# BMCOP.net
KiCad netlist of a schematic drawn in EAGLE
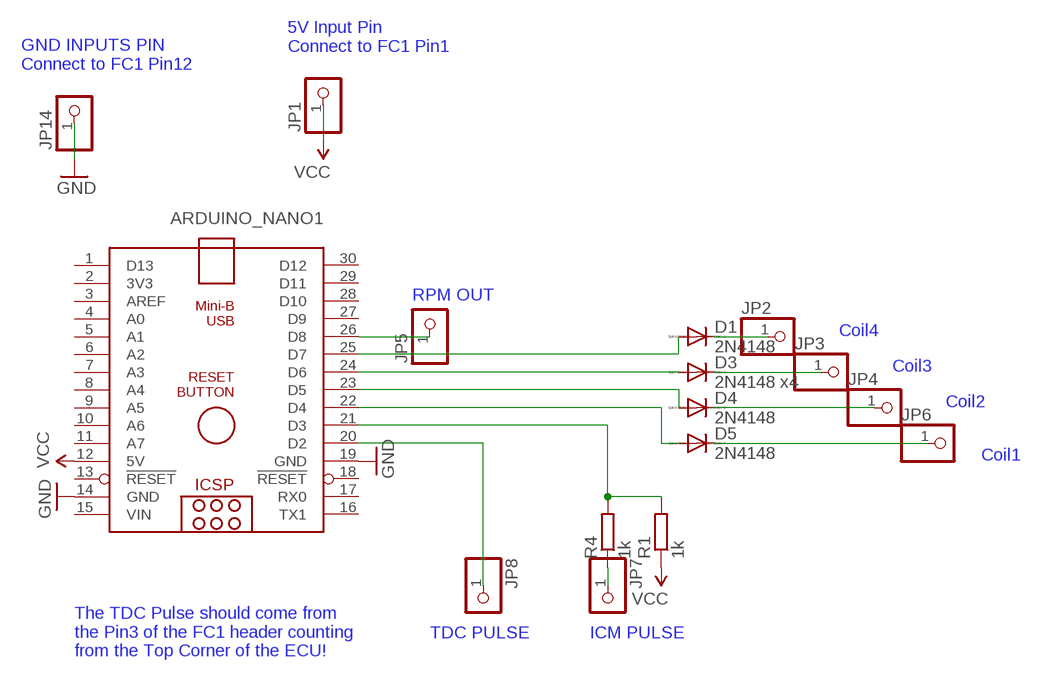
[diagram p0: schematic, sheet 1]

(export (version "E")
  (design (tool "Eeschema 10.0.6"))
  (components
    (comp (ref "ARDUINO_NANO1")
      (value "ARDUINO_NANO")
      (footprint "eagle-import:ARDUINO_NANO")
      (libsource (lib "eagle-import") (part "ARDUINO_NANO"))
    )
    (comp (ref "D1")
      (value "2N4148")
      (footprint "eagle-import:D-7.5")
      (libsource (lib "eagle-import") (part "DIODE-D-7.5"))
    )
    (comp (ref "D3")
      (value "2N4148 x4")
      (footprint "eagle-import:D-7.5")
      (libsource (lib "eagle-import") (part "DIODE-D-7.5"))
    )
    (comp (ref "D4")
      (value "2N4148")
      (footprint "eagle-import:D-7.5")
      (libsource (lib "eagle-import") (part "DIODE-D-7.5"))
    )
    (comp (ref "D5")
      (value "2N4148")
      (footprint "eagle-import:D-7.5")
      (libsource (lib "eagle-import") (part "DIODE-D-7.5"))
    )
    (comp (ref "JP1")
      (value "PINHD-1X1")
      (footprint "eagle-import:1X01")
      (libsource (lib "eagle-import") (part "PINHD-1X1"))
    )
    (comp (ref "JP2")
      (value "PINHD-1X1")
      (footprint "eagle-import:1X01")
      (libsource (lib "eagle-import") (part "PINHD-1X1"))
    )
    (comp (ref "JP3")
      (value "PINHD-1X1")
      (footprint "eagle-import:1X01")
      (libsource (lib "eagle-import") (part "PINHD-1X1"))
    )
    (comp (ref "JP4")
      (value "PINHD-1X1")
      (footprint "eagle-import:1X01")
      (libsource (lib "eagle-import") (part "PINHD-1X1"))
    )
    (comp (ref "JP5")
      (value "PINHD-1X1")
      (footprint "eagle-import:1X01")
      (libsource (lib "eagle-import") (part "PINHD-1X1"))
    )
    (comp (ref "JP6")
      (value "PINHD-1X1")
      (footprint "eagle-import:1X01")
      (libsource (lib "eagle-import") (part "PINHD-1X1"))
    )
    (comp (ref "JP7")
      (value "PINHD-1X1")
      (footprint "eagle-import:1X01")
      (libsource (lib "eagle-import") (part "PINHD-1X1"))
    )
    (comp (ref "JP8")
      (value "PINHD-1X1")
      (footprint "eagle-import:1X01")
      (libsource (lib "eagle-import") (part "PINHD-1X1"))
    )
    (comp (ref "JP14")
      (value "PINHD-1X1")
      (footprint "eagle-import:1X01")
      (libsource (lib "eagle-import") (part "PINHD-1X1"))
    )
    (comp (ref "R1")
      (value "1k")
      (footprint "eagle-import:0204_7")
      (libsource (lib "eagle-import") (part "R-EU_0204/7"))
    )
    (comp (ref "R4")
      (value "1k")
      (footprint "eagle-import:0204_7")
      (libsource (lib "eagle-import") (part "R-EU_0204/7"))
    )
  )
  (nets
    (net (code "1") (name "/VIN") (class "Default")
      (node (ref "ARDUINO_NANO1") (pin "15") (pinfunction "VIN_15") (pintype "power_in"))
    )
    (net (code "2") (name "GND") (class "Default")
      (node (ref "ARDUINO_NANO1") (pin "14") (pinfunction "GND_14") (pintype "power_in"))
      (node (ref "ARDUINO_NANO1") (pin "19") (pinfunction "GND_19") (pintype "power_in"))
      (node (ref "JP14") (pin "1") (pinfunction "1_1") (pintype "passive"))
    )
    (net (code "3") (name "Net-(ARDUINO_NANO1-D2)") (class "Default")
      (node (ref "ARDUINO_NANO1") (pin "20") (pinfunction "D2_20") (pintype "bidirectional"))
      (node (ref "JP8") (pin "1") (pinfunction "1_1") (pintype "passive"))
    )
    (net (code "4") (name "Net-(ARDUINO_NANO1-D3)") (class "Default")
      (node (ref "ARDUINO_NANO1") (pin "21") (pinfunction "D3_21") (pintype "bidirectional"))
      (node (ref "R1") (pin "2") (pinfunction "2_2") (pintype "passive"))
      (node (ref "R4") (pin "2") (pinfunction "2_2") (pintype "passive"))
    )
    (net (code "5") (name "Net-(ARDUINO_NANO1-D4)") (class "Default")
      (node (ref "ARDUINO_NANO1") (pin "22") (pinfunction "D4_22") (pintype "bidirectional"))
      (node (ref "D5") (pin "A") (pinfunction "A_A") (pintype "passive"))
    )
    (net (code "6") (name "Net-(ARDUINO_NANO1-D5)") (class "Default")
      (node (ref "ARDUINO_NANO1") (pin "23") (pinfunction "D5_23") (pintype "bidirectional"))
      (node (ref "D4") (pin "A") (pinfunction "A_A") (pintype "passive"))
    )
    (net (code "7") (name "Net-(ARDUINO_NANO1-D6)") (class "Default")
      (node (ref "ARDUINO_NANO1") (pin "24") (pinfunction "D6_24") (pintype "bidirectional"))
      (node (ref "D3") (pin "A") (pinfunction "A_A") (pintype "passive"))
    )
    (net (code "8") (name "Net-(ARDUINO_NANO1-D7)") (class "Default")
      (node (ref "ARDUINO_NANO1") (pin "25") (pinfunction "D7_25") (pintype "bidirectional"))
      (node (ref "D1") (pin "A") (pinfunction "A_A") (pintype "passive"))
    )
    (net (code "9") (name "Net-(ARDUINO_NANO1-D8)") (class "Default")
      (node (ref "ARDUINO_NANO1") (pin "26") (pinfunction "D8_26") (pintype "bidirectional"))
      (node (ref "JP5") (pin "1") (pinfunction "1_1") (pintype "passive"))
    )
    (net (code "10") (name "Net-(D1-PadC)") (class "Default")
      (node (ref "D1") (pin "C") (pinfunction "C_C") (pintype "passive"))
      (node (ref "JP2") (pin "1") (pinfunction "1_1") (pintype "passive"))
    )
    (net (code "11") (name "Net-(D3-PadC)") (class "Default")
      (node (ref "D3") (pin "C") (pinfunction "C_C") (pintype "passive"))
      (node (ref "JP3") (pin "1") (pinfunction "1_1") (pintype "passive"))
    )
    (net (code "12") (name "Net-(D4-PadC)") (class "Default")
      (node (ref "D4") (pin "C") (pinfunction "C_C") (pintype "passive"))
      (node (ref "JP4") (pin "1") (pinfunction "1_1") (pintype "passive"))
    )
    (net (code "13") (name "Net-(D5-PadC)") (class "Default")
      (node (ref "D5") (pin "C") (pinfunction "C_C") (pintype "passive"))
      (node (ref "JP6") (pin "1") (pinfunction "1_1") (pintype "passive"))
    )
    (net (code "14") (name "Net-(JP7-Pad1)") (class "Default")
      (node (ref "JP7") (pin "1") (pinfunction "1_1") (pintype "passive"))
      (node (ref "R4") (pin "1") (pinfunction "1_1") (pintype "passive"))
    )
    (net (code "15") (name "VCC") (class "Default")
      (node (ref "ARDUINO_NANO1") (pin "12") (pinfunction "5V_12") (pintype "power_in"))
      (node (ref "JP1") (pin "1") (pinfunction "1_1") (pintype "passive"))
      (node (ref "R1") (pin "1") (pinfunction "1_1") (pintype "passive"))
    )
    (net (code "16") (name "unconnected-(ARDUINO_NANO1-3V3-Pad2)") (class "Default")
      (node (ref "ARDUINO_NANO1") (pin "2") (pinfunction "3V3_2") (pintype "output"))
    )
    (net (code "17") (name "unconnected-(ARDUINO_NANO1-A0-Pad4)") (class "Default")
      (node (ref "ARDUINO_NANO1") (pin "4") (pinfunction "A0_4") (pintype "bidirectional"))
    )
    (net (code "18") (name "unconnected-(ARDUINO_NANO1-A1-Pad5)") (class "Default")
      (node (ref "ARDUINO_NANO1") (pin "5") (pinfunction "A1_5") (pintype "bidirectional"))
    )
    (net (code "19") (name "unconnected-(ARDUINO_NANO1-A2-Pad6)") (class "Default")
      (node (ref "ARDUINO_NANO1") (pin "6") (pinfunction "A2_6") (pintype "bidirectional"))
    )
    (net (code "20") (name "unconnected-(ARDUINO_NANO1-A3-Pad7)") (class "Default")
      (node (ref "ARDUINO_NANO1") (pin "7") (pinfunction "A3_7") (pintype "bidirectional"))
    )
    (net (code "21") (name "unconnected-(ARDUINO_NANO1-A4-Pad8)") (class "Default")
      (node (ref "ARDUINO_NANO1") (pin "8") (pinfunction "A4_8") (pintype "bidirectional"))
    )
    (net (code "22") (name "unconnected-(ARDUINO_NANO1-A5-Pad9)") (class "Default")
      (node (ref "ARDUINO_NANO1") (pin "9") (pinfunction "A5_9") (pintype "bidirectional"))
    )
    (net (code "23") (name "unconnected-(ARDUINO_NANO1-A6-Pad10)") (class "Default")
      (node (ref "ARDUINO_NANO1") (pin "10") (pinfunction "A6_10") (pintype "bidirectional"))
    )
    (net (code "24") (name "unconnected-(ARDUINO_NANO1-A7-Pad11)") (class "Default")
      (node (ref "ARDUINO_NANO1") (pin "11") (pinfunction "A7_11") (pintype "bidirectional"))
    )
    (net (code "25") (name "unconnected-(ARDUINO_NANO1-AREF-Pad3)") (class "Default")
      (node (ref "ARDUINO_NANO1") (pin "3") (pinfunction "AREF_3") (pintype "input"))
    )
    (net (code "26") (name "unconnected-(ARDUINO_NANO1-D9-Pad27)") (class "Default")
      (node (ref "ARDUINO_NANO1") (pin "27") (pinfunction "D9_27") (pintype "bidirectional"))
    )
    (net (code "27") (name "unconnected-(ARDUINO_NANO1-D10-Pad28)") (class "Default")
      (node (ref "ARDUINO_NANO1") (pin "28") (pinfunction "D10_28") (pintype "bidirectional"))
    )
    (net (code "28") (name "unconnected-(ARDUINO_NANO1-D11-Pad29)") (class "Default")
      (node (ref "ARDUINO_NANO1") (pin "29") (pinfunction "D11_29") (pintype "bidirectional"))
    )
    (net (code "29") (name "unconnected-(ARDUINO_NANO1-D12-Pad30)") (class "Default")
      (node (ref "ARDUINO_NANO1") (pin "30") (pinfunction "D12_30") (pintype "bidirectional"))
    )
    (net (code "30") (name "unconnected-(ARDUINO_NANO1-D13-Pad1)") (class "Default")
      (node (ref "ARDUINO_NANO1") (pin "1") (pinfunction "D13_1") (pintype "bidirectional"))
    )
    (net (code "31") (name "unconnected-(ARDUINO_NANO1-RX0-Pad17)") (class "Default")
      (node (ref "ARDUINO_NANO1") (pin "17") (pinfunction "RX0_17") (pintype "bidirectional"))
    )
    (net (code "32") (name "unconnected-(ARDUINO_NANO1-TX1-Pad16)") (class "Default")
      (node (ref "ARDUINO_NANO1") (pin "16") (pinfunction "TX1_16") (pintype "bidirectional"))
    )
    (net (code "33") (name "unconnected-(ARDUINO_NANO1-~{RESET}-Pad13)") (class "Default")
      (node (ref "ARDUINO_NANO1") (pin "13") (pinfunction "~{RESET}_13") (pintype "input"))
    )
    (net (code "34") (name "unconnected-(ARDUINO_NANO1-~{RESET}-Pad18)") (class "Default")
      (node (ref "ARDUINO_NANO1") (pin "18") (pinfunction "~{RESET}_18") (pintype "input"))
    )
  )
)
